# LB1836M_breakout.net
KiCad netlist of a schematic drawn in EAGLE
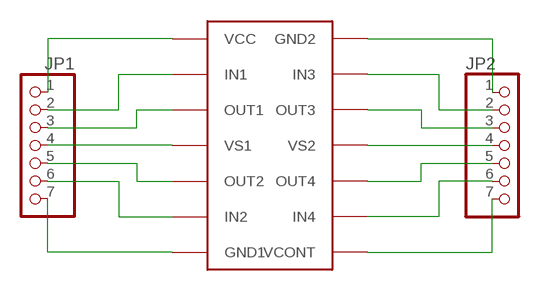
[diagram p0: schematic, sheet 1]

(export (version "E")
  (design (tool "Eeschema 10.0.6"))
  (components
    (comp (ref "JP1")
      (value "PINHD-1X7")
      (footprint "eagle-import:1X07")
      (libsource (lib "eagle-import") (part "PINHD-1X7"))
    )
    (comp (ref "JP2")
      (value "PINHD-1X7")
      (footprint "eagle-import:1X07")
      (libsource (lib "eagle-import") (part "PINHD-1X7"))
    )
    (comp (ref "LB1836M")
      (value "LB1836M")
      (footprint "eagle-import:MFP-14")
      (libsource (lib "eagle-import") (part "LB1836M"))
    )
  )
  (nets
    (net (code "1") (name "Net-(JP1-Pad1)") (class "Default")
      (node (ref "JP1") (pin "1") (pinfunction "1_1") (pintype "passive"))
      (node (ref "LB1836M") (pin "VCC") (pinfunction "VCC_VCC") (pintype "bidirectional"))
    )
    (net (code "2") (name "Net-(JP1-Pad2)") (class "Default")
      (node (ref "JP1") (pin "2") (pinfunction "2_2") (pintype "passive"))
      (node (ref "LB1836M") (pin "IN1") (pinfunction "IN1_IN1") (pintype "bidirectional"))
    )
    (net (code "3") (name "Net-(JP1-Pad3)") (class "Default")
      (node (ref "JP1") (pin "3") (pinfunction "3_3") (pintype "passive"))
      (node (ref "LB1836M") (pin "OUT1") (pinfunction "OUT1_OUT1") (pintype "bidirectional"))
    )
    (net (code "4") (name "Net-(JP1-Pad4)") (class "Default")
      (node (ref "JP1") (pin "4") (pinfunction "4_4") (pintype "passive"))
      (node (ref "LB1836M") (pin "VS1") (pinfunction "VS1_VS1") (pintype "bidirectional"))
    )
    (net (code "5") (name "Net-(JP1-Pad5)") (class "Default")
      (node (ref "JP1") (pin "5") (pinfunction "5_5") (pintype "passive"))
      (node (ref "LB1836M") (pin "OUT2") (pinfunction "OUT2_OUT2") (pintype "bidirectional"))
    )
    (net (code "6") (name "Net-(JP1-Pad6)") (class "Default")
      (node (ref "JP1") (pin "6") (pinfunction "6_6") (pintype "passive"))
      (node (ref "LB1836M") (pin "IN2") (pinfunction "IN2_IN2") (pintype "bidirectional"))
    )
    (net (code "7") (name "Net-(JP1-Pad7)") (class "Default")
      (node (ref "JP1") (pin "7") (pinfunction "7_7") (pintype "passive"))
      (node (ref "LB1836M") (pin "GND1") (pinfunction "GND1_GND1") (pintype "bidirectional"))
    )
    (net (code "8") (name "Net-(JP2-Pad2)") (class "Default")
      (node (ref "JP2") (pin "2") (pinfunction "2_2") (pintype "passive"))
      (node (ref "LB1836M") (pin "IN3") (pinfunction "IN3_IN3") (pintype "bidirectional"))
    )
    (net (code "9") (name "Net-(JP2-Pad3)") (class "Default")
      (node (ref "JP2") (pin "3") (pinfunction "3_3") (pintype "passive"))
      (node (ref "LB1836M") (pin "OUT3") (pinfunction "OUT3_OUT3") (pintype "bidirectional"))
    )
    (net (code "10") (name "Net-(JP2-Pad4)") (class "Default")
      (node (ref "JP2") (pin "4") (pinfunction "4_4") (pintype "passive"))
      (node (ref "LB1836M") (pin "VS2") (pinfunction "VS2_VS2") (pintype "bidirectional"))
    )
    (net (code "11") (name "Net-(JP2-Pad5)") (class "Default")
      (node (ref "JP2") (pin "5") (pinfunction "5_5") (pintype "passive"))
      (node (ref "LB1836M") (pin "OUT4") (pinfunction "OUT4_OUT4") (pintype "bidirectional"))
    )
    (net (code "12") (name "Net-(JP2-Pad6)") (class "Default")
      (node (ref "JP2") (pin "6") (pinfunction "6_6") (pintype "passive"))
      (node (ref "LB1836M") (pin "IN4") (pinfunction "IN4_IN4") (pintype "bidirectional"))
    )
    (net (code "13") (name "Net-(JP2-Pad7)") (class "Default")
      (node (ref "JP2") (pin "7") (pinfunction "7_7") (pintype "passive"))
      (node (ref "LB1836M") (pin "VCONT") (pinfunction "VCONT_VCONT") (pintype "bidirectional"))
    )
    (net (code "14") (name "Net-(LB1836M-GND2)") (class "Default")
      (node (ref "JP2") (pin "1") (pinfunction "1_1") (pintype "passive"))
      (node (ref "LB1836M") (pin "GN2") (pinfunction "GND2_GN2") (pintype "bidirectional"))
    )
  )
)
